# 60-hv-amp-signal-path.net
KiCad netlist of a schematic drawn in EAGLE
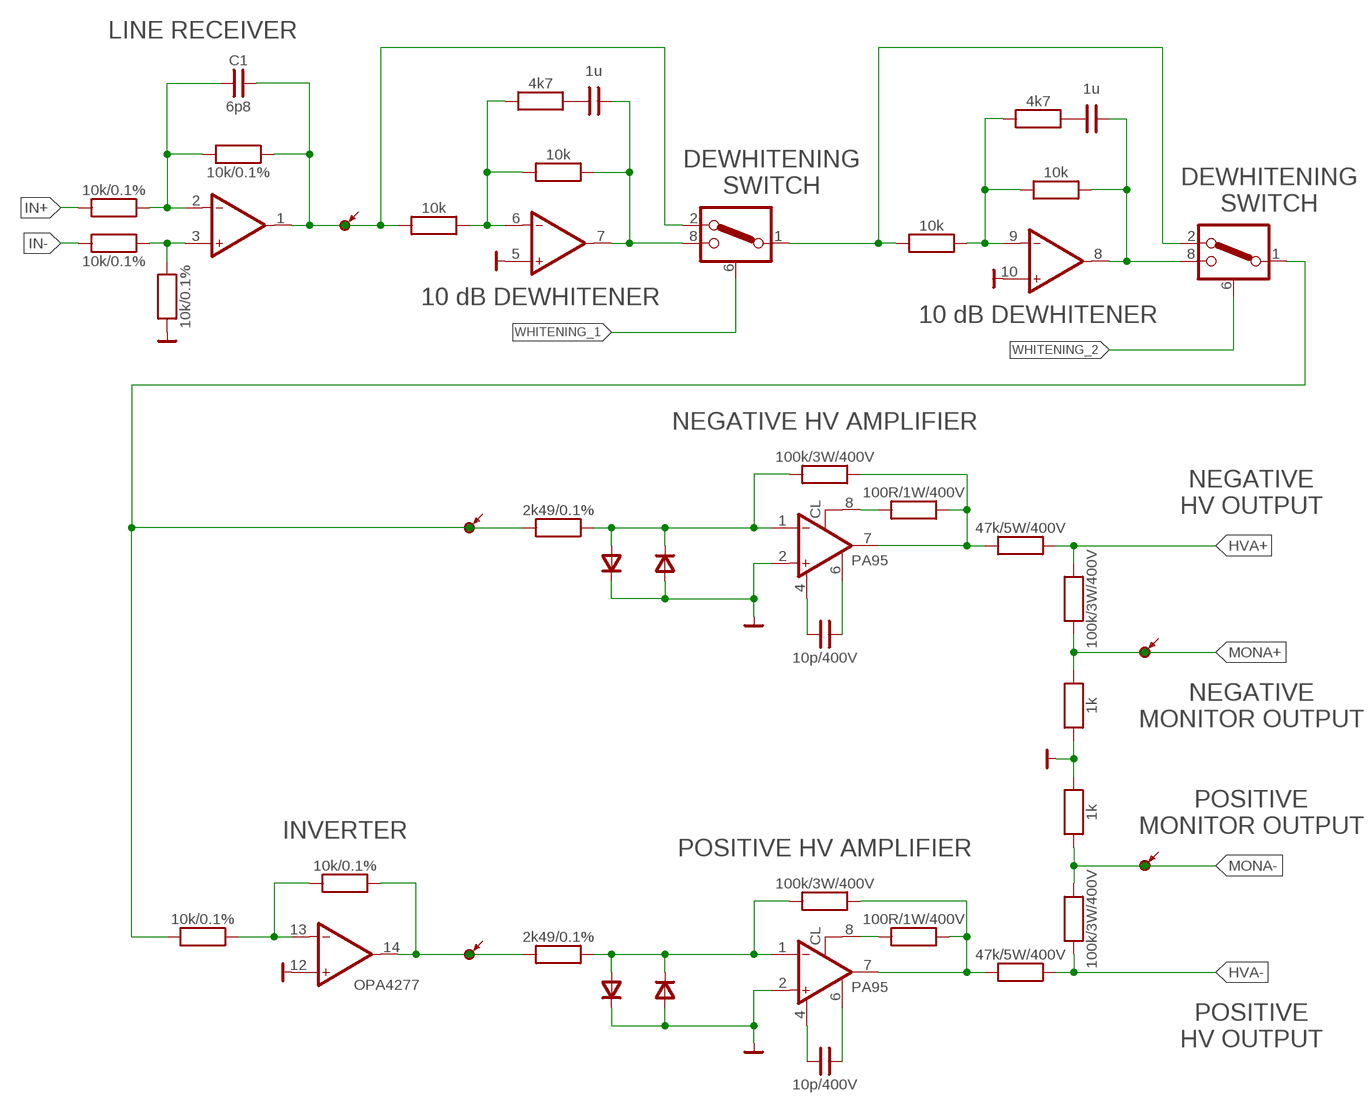
[diagram p0: schematic, sheet 1]

(export (version "E")
  (design (tool "Eeschema 10.0.6"))
  (components
    (comp (ref "C1")
      (value "6p8")
      (footprint "eagle-import:C03N")
      (libsource (lib "eagle-import") (part "C03N"))
    )
    (comp (ref "C5")
      (value "1u")
      (footprint "eagle-import:C02-MKS2-5.0-N")
      (libsource (lib "eagle-import") (part "C02-MKS2-5.0-N"))
    )
    (comp (ref "C9")
      (value "1u")
      (footprint "eagle-import:C02-MKS2-5.0-N")
      (libsource (lib "eagle-import") (part "C02-MKS2-5.0-N"))
    )
    (comp (ref "C13")
      (value "10p/400V")
      (footprint "eagle-import:C03N")
      (libsource (lib "eagle-import") (part "C03N"))
    )
    (comp (ref "C14")
      (value "10p/400V")
      (footprint "eagle-import:C03N")
      (libsource (lib "eagle-import") (part "C03N"))
    )
    (comp (ref "D1")
      (value "1N4148")
      (footprint "eagle-import:D04N-DO35-TYPE")
      (libsource (lib "eagle-import") (part "1N4148-04"))
    )
    (comp (ref "D2")
      (value "1N4148")
      (footprint "eagle-import:D04N-DO35-TYPE")
      (libsource (lib "eagle-import") (part "1N4148-04"))
    )
    (comp (ref "D9")
      (value "1N4148")
      (footprint "eagle-import:D04N-DO35-TYPE")
      (libsource (lib "eagle-import") (part "1N4148-04"))
    )
    (comp (ref "D10")
      (value "1N4148")
      (footprint "eagle-import:D04N-DO35-TYPE")
      (libsource (lib "eagle-import") (part "1N4148-04"))
    )
    (comp (ref "N1")
      (value "OPA4277")
      (footprint "eagle-import:DIP14L")
      (libsource (lib "eagle-import") (part "OPA4277L"))
    )
    (comp (ref "N5")
      (value "MAX4659")
      (footprint "eagle-import:DIP08L")
      (libsource (lib "eagle-import") (part "DG419L"))
    )
    (comp (ref "N9")
      (value "MAX4659")
      (footprint "eagle-import:DIP08L")
      (libsource (lib "eagle-import") (part "DG419L"))
    )
    (comp (ref "N13")
      (value "PA95")
      (footprint "eagle-import:SIP03VR")
      (libsource (lib "eagle-import") (part "PA95"))
    )
    (comp (ref "N14")
      (value "PA95")
      (footprint "eagle-import:SIP03VR")
      (libsource (lib "eagle-import") (part "PA95"))
    )
    (comp (ref "R1")
      (value "10k/0.1%")
      (footprint "eagle-import:R04N")
      (libsource (lib "eagle-import") (part "RN"))
    )
    (comp (ref "R2")
      (value "10k/0.1%")
      (footprint "eagle-import:R04N")
      (libsource (lib "eagle-import") (part "RN"))
    )
    (comp (ref "R9")
      (value "10k/0.1%")
      (footprint "eagle-import:R04N")
      (libsource (lib "eagle-import") (part "RN"))
    )
    (comp (ref "R13")
      (value "10k/0.1%")
      (footprint "eagle-import:R04N")
      (libsource (lib "eagle-import") (part "RN"))
    )
    (comp (ref "R17")
      (value "10k")
      (footprint "eagle-import:R04N")
      (libsource (lib "eagle-import") (part "RN"))
    )
    (comp (ref "R21")
      (value "4k7")
      (footprint "eagle-import:R04N")
      (libsource (lib "eagle-import") (part "RN"))
    )
    (comp (ref "R25")
      (value "10k")
      (footprint "eagle-import:R04N")
      (libsource (lib "eagle-import") (part "RN"))
    )
    (comp (ref "R29")
      (value "10k")
      (footprint "eagle-import:R04N")
      (libsource (lib "eagle-import") (part "RN"))
    )
    (comp (ref "R33")
      (value "4k7")
      (footprint "eagle-import:R04N")
      (libsource (lib "eagle-import") (part "RN"))
    )
    (comp (ref "R37")
      (value "10k")
      (footprint "eagle-import:R04N")
      (libsource (lib "eagle-import") (part "RN"))
    )
    (comp (ref "R41")
      (value "10k/0.1%")
      (footprint "eagle-import:R04N")
      (libsource (lib "eagle-import") (part "RN"))
    )
    (comp (ref "R45")
      (value "10k/0.1%")
      (footprint "eagle-import:R04N")
      (libsource (lib "eagle-import") (part "RN"))
    )
    (comp (ref "R49")
      (value "2k49/0.1%")
      (footprint "eagle-import:R04N")
      (libsource (lib "eagle-import") (part "RN"))
    )
    (comp (ref "R50")
      (value "2k49/0.1%")
      (footprint "eagle-import:R04N")
      (libsource (lib "eagle-import") (part "RN"))
    )
    (comp (ref "R57")
      (value "100k/3W/400V")
      (footprint "eagle-import:R05-1W")
      (libsource (lib "eagle-import") (part "R05-1W"))
    )
    (comp (ref "R58")
      (value "100k/3W/400V")
      (footprint "eagle-import:R05-1W")
      (libsource (lib "eagle-import") (part "R05-1W"))
    )
    (comp (ref "R65")
      (value "100R/1W/400V")
      (footprint "eagle-import:R04-1W")
      (libsource (lib "eagle-import") (part "R04-1W"))
    )
    (comp (ref "R66")
      (value "100R/1W/400V")
      (footprint "eagle-import:R04-1W")
      (libsource (lib "eagle-import") (part "R04-1W"))
    )
    (comp (ref "R73")
      (value "47k/5W/400V")
      (footprint "eagle-import:R04-1W")
      (libsource (lib "eagle-import") (part "R04-1W"))
    )
    (comp (ref "R74")
      (value "47k/5W/400V")
      (footprint "eagle-import:R04-1W")
      (libsource (lib "eagle-import") (part "R04-1W"))
    )
    (comp (ref "R81")
      (value "100k/3W/400V")
      (footprint "eagle-import:R05-1W")
      (libsource (lib "eagle-import") (part "R05-1W"))
    )
    (comp (ref "R82")
      (value "1k")
      (footprint "eagle-import:R04N")
      (libsource (lib "eagle-import") (part "R04"))
    )
    (comp (ref "R83")
      (value "1k")
      (footprint "eagle-import:R04N")
      (libsource (lib "eagle-import") (part "R04"))
    )
    (comp (ref "R84")
      (value "100k/3W/400V")
      (footprint "eagle-import:R05-1W")
      (libsource (lib "eagle-import") (part "R05-1W"))
    )
    (comp (ref "X1")
      (value "IN")
      (footprint "eagle-import:XT-0.8CERAM-N")
      (libsource (lib "eagle-import") (part "XT-0.8CERAM-N"))
    )
    (comp (ref "X5")
      (value "HV_IN+")
      (footprint "eagle-import:XT-0.8CERAM-N")
      (libsource (lib "eagle-import") (part "XT-0.8CERAM-N"))
    )
    (comp (ref "X6")
      (value "HV_IN-")
      (footprint "eagle-import:XT-0.8CERAM-N")
      (libsource (lib "eagle-import") (part "XT-0.8CERAM-N"))
    )
    (comp (ref "X13")
      (value "MON+")
      (footprint "eagle-import:XT-0.8CERAM-N")
      (libsource (lib "eagle-import") (part "XT-0.8CERAM-N"))
    )
    (comp (ref "X14")
      (value "MON-")
      (footprint "eagle-import:XT-0.8CERAM-N")
      (libsource (lib "eagle-import") (part "XT-0.8CERAM-N"))
    )
  )
  (nets
    (net (code "1") (name "HVA+") (class "Default")
      (node (ref "R73") (pin "2") (pinfunction "2_2") (pintype "passive"))
      (node (ref "R81") (pin "2") (pinfunction "2_2") (pintype "passive"))
    )
    (net (code "2") (name "HVA-") (class "Default")
      (node (ref "R74") (pin "2") (pinfunction "2_2") (pintype "passive"))
      (node (ref "R84") (pin "1") (pinfunction "1_1") (pintype "passive"))
    )
    (net (code "3") (name "IN+") (class "Default")
      (node (ref "R1") (pin "1") (pinfunction "1_1") (pintype "passive"))
    )
    (net (code "4") (name "IN-") (class "Default")
      (node (ref "R2") (pin "1") (pinfunction "1_1") (pintype "passive"))
    )
    (net (code "5") (name "MONA+") (class "Default")
      (node (ref "R81") (pin "1") (pinfunction "1_1") (pintype "passive"))
      (node (ref "R82") (pin "2") (pinfunction "2_2") (pintype "passive"))
      (node (ref "X13") (pin "MP") (pinfunction "MP_MP") (pintype "bidirectional"))
    )
    (net (code "6") (name "MONA-") (class "Default")
      (node (ref "R83") (pin "1") (pinfunction "1_1") (pintype "passive"))
      (node (ref "R84") (pin "2") (pinfunction "2_2") (pintype "passive"))
      (node (ref "X14") (pin "MP") (pinfunction "MP_MP") (pintype "bidirectional"))
    )
    (net (code "7") (name "Net-(C5-Pad1)") (class "Default")
      (node (ref "C5") (pin "1") (pinfunction "1_1") (pintype "passive"))
      (node (ref "R21") (pin "2") (pinfunction "2_2") (pintype "passive"))
    )
    (net (code "8") (name "Net-(C9-Pad1)") (class "Default")
      (node (ref "C9") (pin "1") (pinfunction "1_1") (pintype "passive"))
      (node (ref "R33") (pin "2") (pinfunction "2_2") (pintype "passive"))
    )
    (net (code "9") (name "Net-(N1A-IN+)") (class "Default")
      (node (ref "N1") (pin "3") (pinfunction "IN+_3") (pintype "input"))
      (node (ref "R2") (pin "2") (pinfunction "2_2") (pintype "passive"))
      (node (ref "R9") (pin "2") (pinfunction "2_2") (pintype "passive"))
    )
    (net (code "10") (name "Net-(N1A-IN-)") (class "Default")
      (node (ref "C1") (pin "1") (pinfunction "1_1") (pintype "passive"))
      (node (ref "N1") (pin "2") (pinfunction "IN-_2") (pintype "input"))
      (node (ref "R1") (pin "2") (pinfunction "2_2") (pintype "passive"))
      (node (ref "R13") (pin "1") (pinfunction "1_1") (pintype "passive"))
    )
    (net (code "11") (name "Net-(N1A-OUT)") (class "Default")
      (node (ref "C1") (pin "2") (pinfunction "2_2") (pintype "passive"))
      (node (ref "N1") (pin "1") (pinfunction "OUT_1") (pintype "output"))
      (node (ref "N5") (pin "2") (pinfunction "S2A_2") (pintype "bidirectional"))
      (node (ref "R13") (pin "2") (pinfunction "2_2") (pintype "passive"))
      (node (ref "R17") (pin "1") (pinfunction "1_1") (pintype "passive"))
      (node (ref "X1") (pin "MP") (pinfunction "MP_MP") (pintype "bidirectional"))
    )
    (net (code "12") (name "Net-(N1B-IN-)") (class "Default")
      (node (ref "N1") (pin "6") (pinfunction "IN-_6") (pintype "input"))
      (node (ref "R17") (pin "2") (pinfunction "2_2") (pintype "passive"))
      (node (ref "R21") (pin "1") (pinfunction "1_1") (pintype "passive"))
      (node (ref "R25") (pin "1") (pinfunction "1_1") (pintype "passive"))
    )
    (net (code "13") (name "Net-(N1B-OUT)") (class "Default")
      (node (ref "C5") (pin "2") (pinfunction "2_2") (pintype "passive"))
      (node (ref "N1") (pin "7") (pinfunction "OUT_7") (pintype "output"))
      (node (ref "N5") (pin "8") (pinfunction "S2B_8") (pintype "bidirectional"))
      (node (ref "R25") (pin "2") (pinfunction "2_2") (pintype "passive"))
    )
    (net (code "14") (name "Net-(N1C-IN-)") (class "Default")
      (node (ref "N1") (pin "9") (pinfunction "IN-_9") (pintype "input"))
      (node (ref "R29") (pin "2") (pinfunction "2_2") (pintype "passive"))
      (node (ref "R33") (pin "1") (pinfunction "1_1") (pintype "passive"))
      (node (ref "R37") (pin "1") (pinfunction "1_1") (pintype "passive"))
    )
    (net (code "15") (name "Net-(N1C-OUT)") (class "Default")
      (node (ref "C9") (pin "2") (pinfunction "2_2") (pintype "passive"))
      (node (ref "N1") (pin "8") (pinfunction "OUT_8") (pintype "output"))
      (node (ref "N9") (pin "8") (pinfunction "S2B_8") (pintype "bidirectional"))
      (node (ref "R37") (pin "2") (pinfunction "2_2") (pintype "passive"))
    )
    (net (code "16") (name "Net-(N1D-IN-)") (class "Default")
      (node (ref "N1") (pin "13") (pinfunction "IN-_13") (pintype "input"))
      (node (ref "R41") (pin "2") (pinfunction "2_2") (pintype "passive"))
      (node (ref "R45") (pin "1") (pinfunction "1_1") (pintype "passive"))
    )
    (net (code "17") (name "Net-(N1D-OUT)") (class "Default")
      (node (ref "N1") (pin "14") (pinfunction "OUT_14") (pintype "output"))
      (node (ref "R45") (pin "2") (pinfunction "2_2") (pintype "passive"))
      (node (ref "R50") (pin "1") (pinfunction "1_1") (pintype "passive"))
      (node (ref "X6") (pin "MP") (pinfunction "MP_MP") (pintype "bidirectional"))
    )
    (net (code "18") (name "Net-(N5A-S1)") (class "Default")
      (node (ref "N5") (pin "1") (pinfunction "S1_1") (pintype "bidirectional"))
      (node (ref "N9") (pin "2") (pinfunction "S2A_2") (pintype "bidirectional"))
      (node (ref "R29") (pin "1") (pinfunction "1_1") (pintype "passive"))
    )
    (net (code "19") (name "Net-(N9A-S1)") (class "Default")
      (node (ref "N9") (pin "1") (pinfunction "S1_1") (pintype "bidirectional"))
      (node (ref "R41") (pin "1") (pinfunction "1_1") (pintype "passive"))
      (node (ref "R49") (pin "1") (pinfunction "1_1") (pintype "passive"))
      (node (ref "X5") (pin "MP") (pinfunction "MP_MP") (pintype "bidirectional"))
    )
    (net (code "20") (name "Net-(N13A-CC1)") (class "Default")
      (node (ref "C13") (pin "1") (pinfunction "1_1") (pintype "passive"))
      (node (ref "N13") (pin "4") (pinfunction "CC1_4") (pintype "bidirectional"))
    )
    (net (code "21") (name "Net-(N13A-CC2)") (class "Default")
      (node (ref "C13") (pin "2") (pinfunction "2_2") (pintype "passive"))
      (node (ref "N13") (pin "6") (pinfunction "CC2_6") (pintype "bidirectional"))
    )
    (net (code "22") (name "Net-(N13A-ILIM)") (class "Default")
      (node (ref "N13") (pin "8") (pinfunction "ILIM_8") (pintype "bidirectional"))
      (node (ref "R65") (pin "1") (pinfunction "1_1") (pintype "passive"))
    )
    (net (code "23") (name "Net-(N13A-IN-)") (class "Default")
      (node (ref "D1") (pin "A") (pinfunction "A_A") (pintype "passive"))
      (node (ref "D9") (pin "C") (pinfunction "C_C") (pintype "passive"))
      (node (ref "N13") (pin "1") (pinfunction "IN-_1") (pintype "input"))
      (node (ref "R49") (pin "2") (pinfunction "2_2") (pintype "passive"))
      (node (ref "R57") (pin "1") (pinfunction "1_1") (pintype "passive"))
    )
    (net (code "24") (name "Net-(N13A-OUT)") (class "Default")
      (node (ref "N13") (pin "7") (pinfunction "OUT_7") (pintype "output"))
      (node (ref "R57") (pin "2") (pinfunction "2_2") (pintype "passive"))
      (node (ref "R65") (pin "2") (pinfunction "2_2") (pintype "passive"))
      (node (ref "R73") (pin "1") (pinfunction "1_1") (pintype "passive"))
    )
    (net (code "25") (name "Net-(N14A-CC1)") (class "Default")
      (node (ref "C14") (pin "1") (pinfunction "1_1") (pintype "passive"))
      (node (ref "N14") (pin "4") (pinfunction "CC1_4") (pintype "bidirectional"))
    )
    (net (code "26") (name "Net-(N14A-CC2)") (class "Default")
      (node (ref "C14") (pin "2") (pinfunction "2_2") (pintype "passive"))
      (node (ref "N14") (pin "6") (pinfunction "CC2_6") (pintype "bidirectional"))
    )
    (net (code "27") (name "Net-(N14A-ILIM)") (class "Default")
      (node (ref "N14") (pin "8") (pinfunction "ILIM_8") (pintype "bidirectional"))
      (node (ref "R66") (pin "1") (pinfunction "1_1") (pintype "passive"))
    )
    (net (code "28") (name "Net-(N14A-IN-)") (class "Default")
      (node (ref "D10") (pin "C") (pinfunction "C_C") (pintype "passive"))
      (node (ref "D2") (pin "A") (pinfunction "A_A") (pintype "passive"))
      (node (ref "N14") (pin "1") (pinfunction "IN-_1") (pintype "input"))
      (node (ref "R50") (pin "2") (pinfunction "2_2") (pintype "passive"))
      (node (ref "R58") (pin "1") (pinfunction "1_1") (pintype "passive"))
    )
    (net (code "29") (name "Net-(N14A-OUT)") (class "Default")
      (node (ref "N14") (pin "7") (pinfunction "OUT_7") (pintype "output"))
      (node (ref "R58") (pin "2") (pinfunction "2_2") (pintype "passive"))
      (node (ref "R66") (pin "2") (pinfunction "2_2") (pintype "passive"))
      (node (ref "R74") (pin "1") (pinfunction "1_1") (pintype "passive"))
    )
    (net (code "30") (name "VG") (class "Default")
      (node (ref "D1") (pin "C") (pinfunction "C_C") (pintype "passive"))
      (node (ref "D10") (pin "A") (pinfunction "A_A") (pintype "passive"))
      (node (ref "D2") (pin "C") (pinfunction "C_C") (pintype "passive"))
      (node (ref "D9") (pin "A") (pinfunction "A_A") (pintype "passive"))
      (node (ref "N1") (pin "10") (pinfunction "IN+_10") (pintype "input"))
      (node (ref "N1") (pin "12") (pinfunction "IN+_12") (pintype "input"))
      (node (ref "N1") (pin "5") (pinfunction "IN+_5") (pintype "input"))
      (node (ref "N13") (pin "2") (pinfunction "IN+_2") (pintype "input"))
      (node (ref "N14") (pin "2") (pinfunction "IN+_2") (pintype "input"))
      (node (ref "R82") (pin "1") (pinfunction "1_1") (pintype "passive"))
      (node (ref "R83") (pin "2") (pinfunction "2_2") (pintype "passive"))
      (node (ref "R9") (pin "1") (pinfunction "1_1") (pintype "passive"))
    )
    (net (code "31") (name "WHITENING_1") (class "Default")
      (node (ref "N5") (pin "6") (pinfunction "D_6") (pintype "input"))
    )
    (net (code "32") (name "WHITENING_2") (class "Default")
      (node (ref "N9") (pin "6") (pinfunction "D_6") (pintype "input"))
    )
  )
)
